# escape-room-riddle-box-11-22_15-05-31.net
KiCad netlist of a schematic drawn in EasyEDA
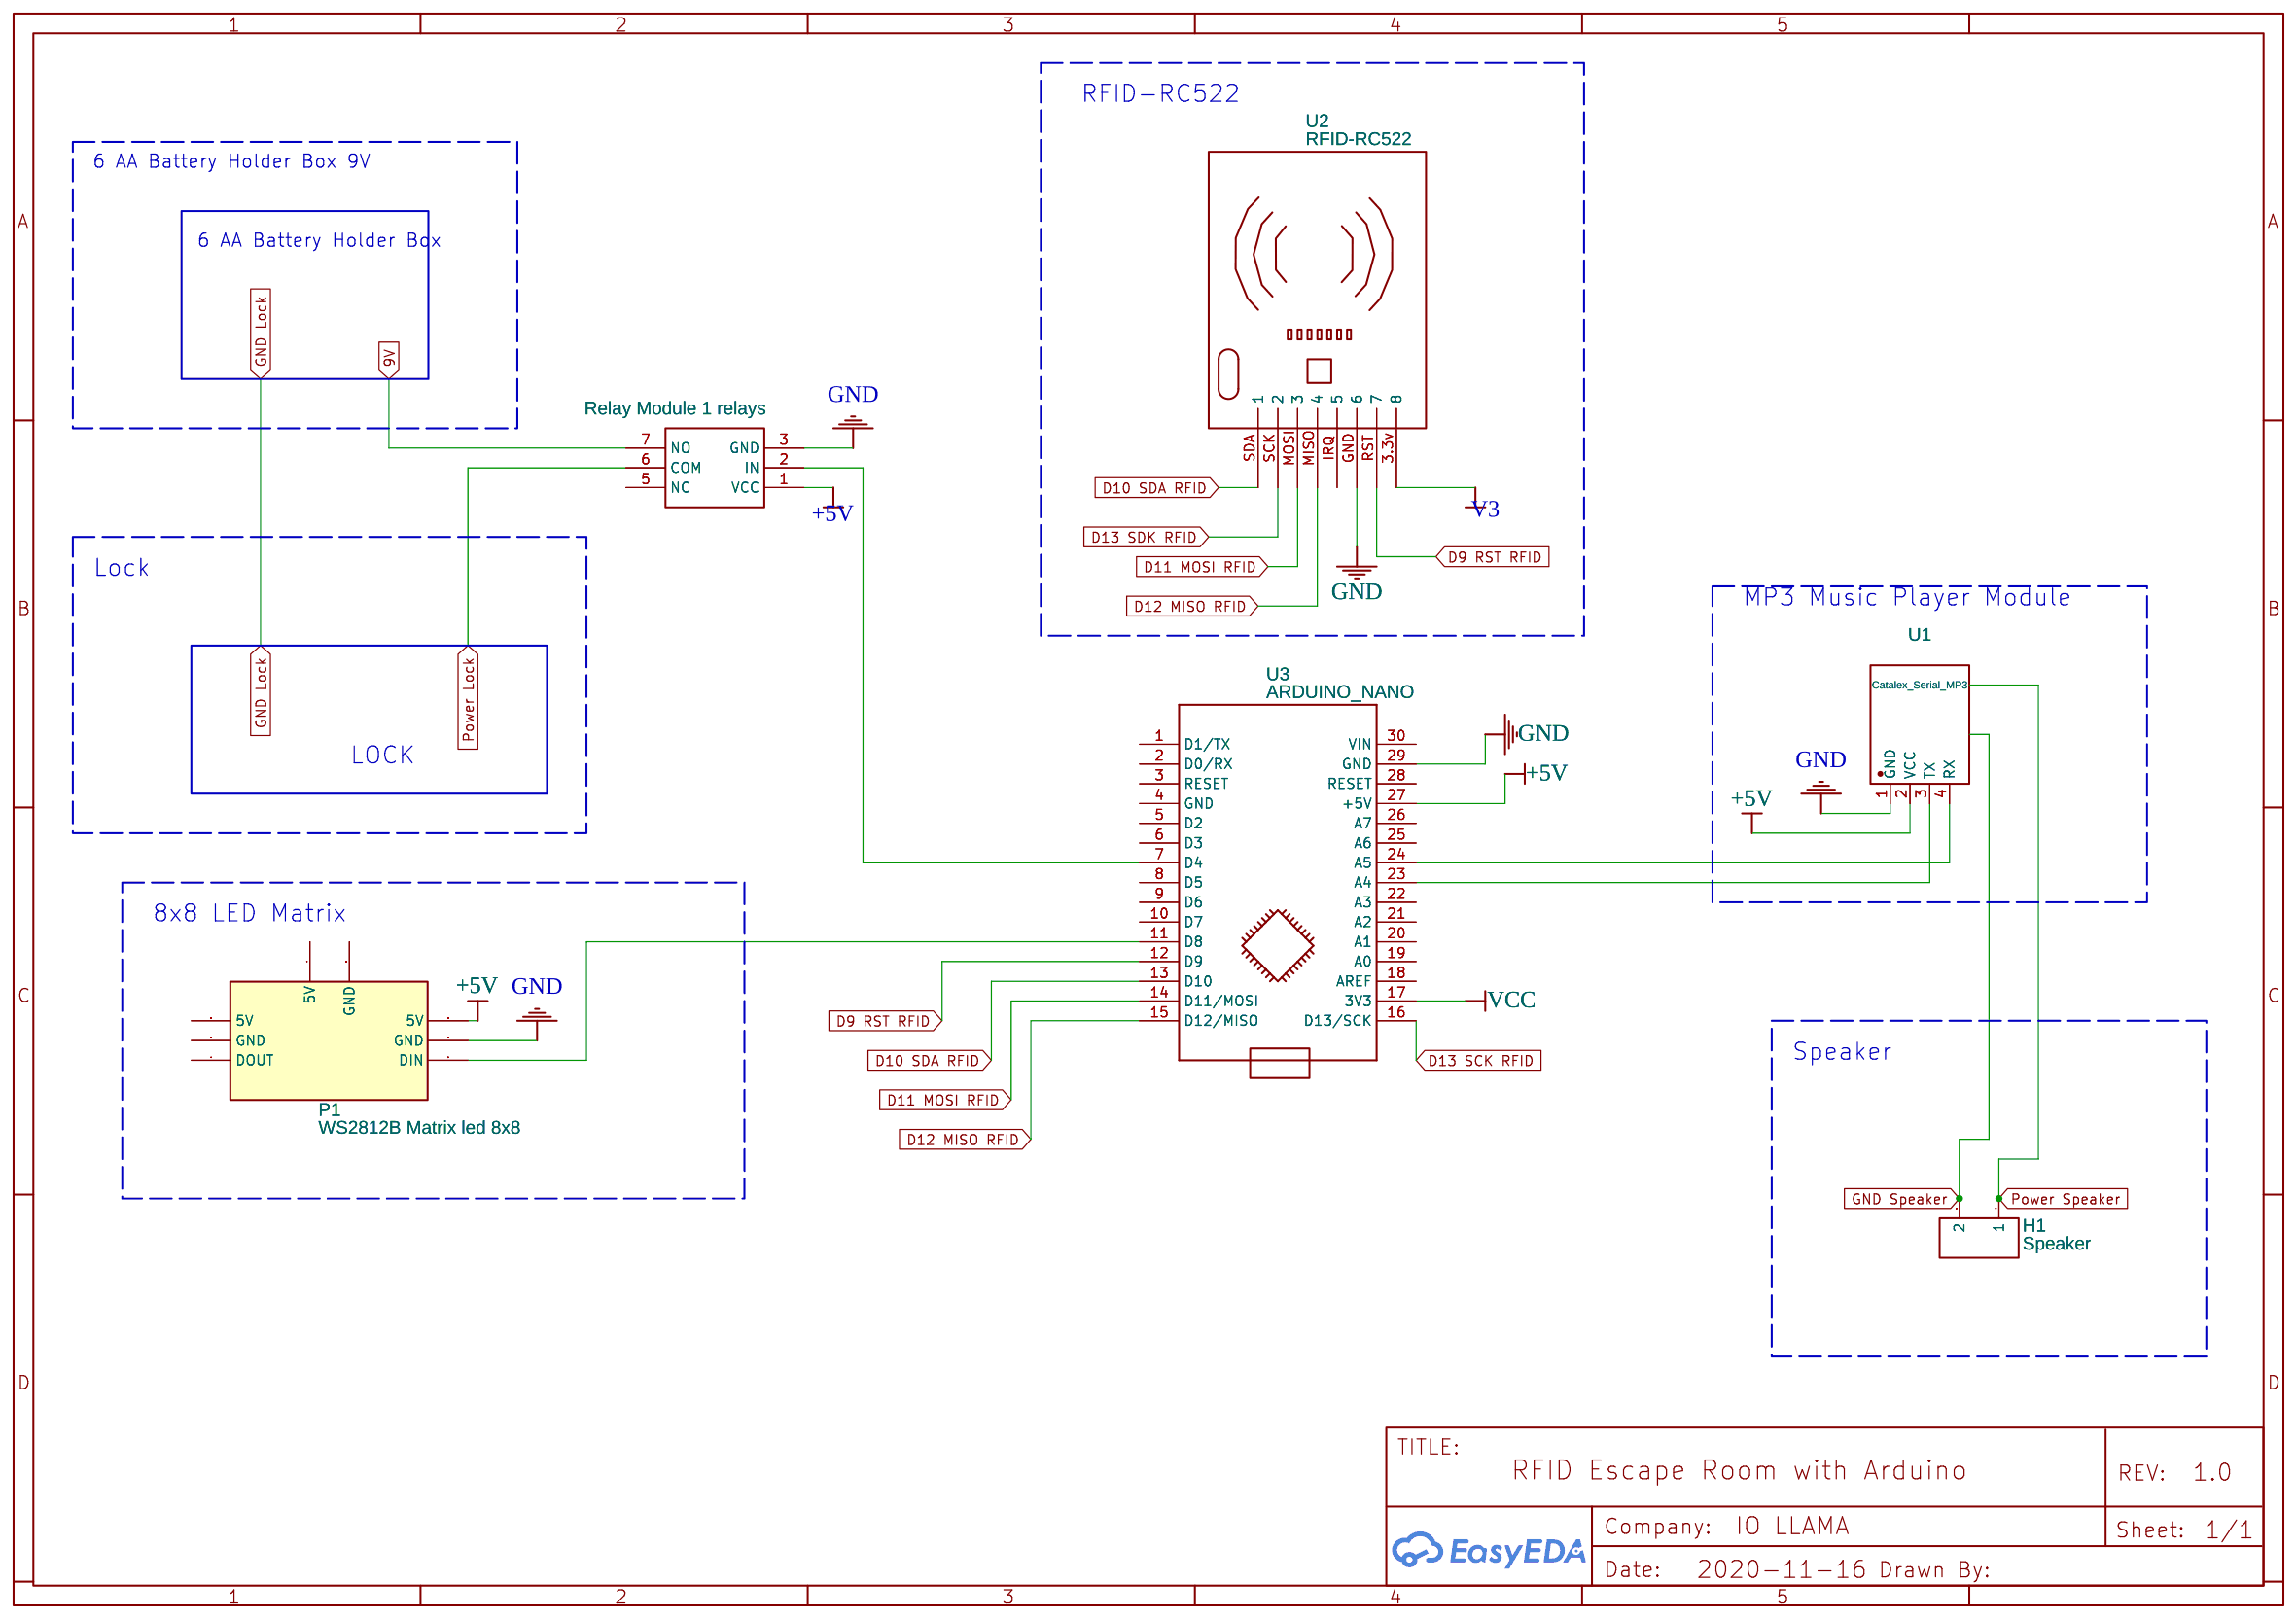
[diagram p0: schematic sheet]

(export (version "E")
  (design (tool "Eeschema 10.0.6"))
  (components
    (comp (ref "H1")
      (value "Speaker")
      (fields (field (name "BOM_Manufacturer Part") "826629-2") (field (name "BOM_Supplier Part") "C86471"))
      (libsource (lib "") (part "Header-Male-2.54_1x2"))
    )
    (comp (ref "P1") (value "WS2812B Matrix led 8x8") (libsource (lib "") (part "WS2812B Matrix led 8x8")))
    (comp (ref "U1")
      (value "Catalex_Serial_MP3")
      (fields (field (name "BOM_Manufacturer Part") "Catalex_Serial_MP3_Board"))
      (libsource (lib "") (part "Catalex_Serial_MP3"))
    )
    (comp (ref "U2")
      (value "RFID-RC522")
      (fields (field (name "BOM_Manufacturer Part") "NXP"))
      (libsource (lib "") (part "RFID-RC522"))
    )
    (comp (ref "U3") (value "ARDUINO_NANO") (libsource (lib "") (part "ARDUINO_NANO")))
    (comp (ref "U4") (value "Relay Module 1 relays") (libsource (lib "") (part "Relay Module 1 relays")))
  )
  (nets
    (net (code "1") (name "+5V") (class "Default")
      (node (ref "P1") (pin "3") (pinfunction "5V_3") (pintype "unspecified"))
      (node (ref "U1") (pin "2") (pinfunction "VCC_2") (pintype "unspecified"))
      (node (ref "U3") (pin "27") (pinfunction "+5V_27") (pintype "unspecified"))
      (node (ref "U4") (pin "1") (pinfunction "VCC_1") (pintype "unspecified"))
    )
    (net (code "2") (name "9V") (class "Default")
      (node (ref "U4") (pin "7") (pinfunction "NO_7") (pintype "unspecified"))
    )
    (net (code "3") (name "D9 RST RFID") (class "Default")
      (node (ref "U2") (pin "RST") (pinfunction "7_RST") (pintype "unspecified"))
      (node (ref "U3") (pin "12") (pinfunction "D9_12") (pintype "unspecified"))
    )
    (net (code "4") (name "D10 SDA RFID") (class "Default")
      (node (ref "U2") (pin "SDA") (pinfunction "1_SDA") (pintype "unspecified"))
      (node (ref "U3") (pin "13") (pinfunction "D10_13") (pintype "unspecified"))
    )
    (net (code "5") (name "D11 MOSI RFID") (class "Default")
      (node (ref "U2") (pin "MOSI") (pinfunction "3_MOSI") (pintype "unspecified"))
      (node (ref "U3") (pin "14") (pinfunction "D11/MOSI_14") (pintype "unspecified"))
    )
    (net (code "6") (name "D12 MISO RFID") (class "Default")
      (node (ref "U2") (pin "MISO") (pinfunction "4_MISO") (pintype "unspecified"))
      (node (ref "U3") (pin "15") (pinfunction "D12/MISO_15") (pintype "unspecified"))
    )
    (net (code "7") (name "D13 SCK RFID") (class "Default")
      (node (ref "U3") (pin "16") (pinfunction "D13/SCK_16") (pintype "unspecified"))
    )
    (net (code "8") (name "D13 SDK RFID") (class "Default")
      (node (ref "U2") (pin "SCK") (pinfunction "2_SCK") (pintype "unspecified"))
    )
    (net (code "9") (name "GND") (class "Default")
      (node (ref "P1") (pin "2") (pinfunction "GND_2") (pintype "unspecified"))
      (node (ref "U1") (pin "1") (pinfunction "GND_1") (pintype "unspecified"))
      (node (ref "U2") (pin "GND") (pinfunction "6_GND") (pintype "unspecified"))
      (node (ref "U3") (pin "29") (pinfunction "GND_29") (pintype "unspecified"))
      (node (ref "U4") (pin "3") (pinfunction "GND_3") (pintype "unspecified"))
    )
    (net (code "11") (name "GND Speaker") (class "Default")
      (node (ref "H1") (pin "2") (pinfunction "2_2") (pintype "unspecified"))
    )
    (net (code "12") (name "Net-(P1-DIN)") (class "Default")
      (node (ref "P1") (pin "1") (pinfunction "DIN_1") (pintype "unspecified"))
      (node (ref "U3") (pin "11") (pinfunction "D8_11") (pintype "unspecified"))
    )
    (net (code "13") (name "Net-(U1-RX)") (class "Default")
      (node (ref "U1") (pin "4") (pinfunction "RX_4") (pintype "unspecified"))
      (node (ref "U3") (pin "24") (pinfunction "A5_24") (pintype "unspecified"))
    )
    (net (code "14") (name "Net-(U1-TX)") (class "Default")
      (node (ref "U1") (pin "3") (pinfunction "TX_3") (pintype "unspecified"))
      (node (ref "U3") (pin "23") (pinfunction "A4_23") (pintype "unspecified"))
    )
    (net (code "15") (name "Net-(U3-D4)") (class "Default")
      (node (ref "U3") (pin "7") (pinfunction "D4_7") (pintype "unspecified"))
      (node (ref "U4") (pin "2") (pinfunction "IN_2") (pintype "unspecified"))
    )
    (net (code "16") (name "Power Lock") (class "Default")
      (node (ref "U4") (pin "6") (pinfunction "COM_6") (pintype "unspecified"))
    )
    (net (code "17") (name "Power Speaker") (class "Default")
      (node (ref "H1") (pin "1") (pinfunction "1_1") (pintype "unspecified"))
    )
    (net (code "18") (name "V3") (class "Default")
      (node (ref "U2") (pin "3.3v") (pinfunction "8_3.3v") (pintype "unspecified"))
    )
    (net (code "19") (name "VCC") (class "Default")
      (node (ref "U3") (pin "17") (pinfunction "3V3_17") (pintype "unspecified"))
    )
    (net (code "20") (name "unconnected-(P1-5V-Pad6)") (class "Default")
      (node (ref "P1") (pin "6") (pinfunction "5V_6") (pintype "unspecified"))
    )
    (net (code "21") (name "unconnected-(P1-5V-Pad7)") (class "Default")
      (node (ref "P1") (pin "7") (pinfunction "5V_7") (pintype "unspecified"))
    )
    (net (code "22") (name "unconnected-(P1-DOUT-Pad4)") (class "Default")
      (node (ref "P1") (pin "4") (pinfunction "DOUT_4") (pintype "unspecified"))
    )
    (net (code "23") (name "unconnected-(P1-GND-Pad5)") (class "Default")
      (node (ref "P1") (pin "5") (pinfunction "GND_5") (pintype "unspecified"))
    )
    (net (code "24") (name "unconnected-(P1-GND-Pad8)") (class "Default")
      (node (ref "P1") (pin "8") (pinfunction "GND_8") (pintype "unspecified"))
    )
    (net (code "25") (name "unconnected-(U2-5-PadIRQ)") (class "Default")
      (node (ref "U2") (pin "IRQ") (pinfunction "5_IRQ") (pintype "unspecified"))
    )
    (net (code "26") (name "unconnected-(U3-A0-Pad19)") (class "Default")
      (node (ref "U3") (pin "19") (pinfunction "A0_19") (pintype "unspecified"))
    )
    (net (code "27") (name "unconnected-(U3-A1-Pad20)") (class "Default")
      (node (ref "U3") (pin "20") (pinfunction "A1_20") (pintype "unspecified"))
    )
    (net (code "28") (name "unconnected-(U3-A2-Pad21)") (class "Default")
      (node (ref "U3") (pin "21") (pinfunction "A2_21") (pintype "unspecified"))
    )
    (net (code "29") (name "unconnected-(U3-A3-Pad22)") (class "Default")
      (node (ref "U3") (pin "22") (pinfunction "A3_22") (pintype "unspecified"))
    )
    (net (code "30") (name "unconnected-(U3-A6-Pad25)") (class "Default")
      (node (ref "U3") (pin "25") (pinfunction "A6_25") (pintype "unspecified"))
    )
    (net (code "31") (name "unconnected-(U3-A7-Pad26)") (class "Default")
      (node (ref "U3") (pin "26") (pinfunction "A7_26") (pintype "unspecified"))
    )
    (net (code "32") (name "unconnected-(U3-AREF-Pad18)") (class "Default")
      (node (ref "U3") (pin "18") (pinfunction "AREF_18") (pintype "unspecified"))
    )
    (net (code "33") (name "unconnected-(U3-D0{slash}RX-Pad2)") (class "Default")
      (node (ref "U3") (pin "2") (pinfunction "D0/RX_2") (pintype "unspecified"))
    )
    (net (code "34") (name "unconnected-(U3-D1{slash}TX-Pad1)") (class "Default")
      (node (ref "U3") (pin "1") (pinfunction "D1/TX_1") (pintype "unspecified"))
    )
    (net (code "35") (name "unconnected-(U3-D2-Pad5)") (class "Default")
      (node (ref "U3") (pin "5") (pinfunction "D2_5") (pintype "unspecified"))
    )
    (net (code "36") (name "unconnected-(U3-D3-Pad6)") (class "Default")
      (node (ref "U3") (pin "6") (pinfunction "D3_6") (pintype "unspecified"))
    )
    (net (code "37") (name "unconnected-(U3-D5-Pad8)") (class "Default")
      (node (ref "U3") (pin "8") (pinfunction "D5_8") (pintype "unspecified"))
    )
    (net (code "38") (name "unconnected-(U3-D6-Pad9)") (class "Default")
      (node (ref "U3") (pin "9") (pinfunction "D6_9") (pintype "unspecified"))
    )
    (net (code "39") (name "unconnected-(U3-D7-Pad10)") (class "Default")
      (node (ref "U3") (pin "10") (pinfunction "D7_10") (pintype "unspecified"))
    )
    (net (code "40") (name "unconnected-(U3-GND-Pad4)") (class "Default")
      (node (ref "U3") (pin "4") (pinfunction "GND_4") (pintype "unspecified"))
    )
    (net (code "41") (name "unconnected-(U3-RESET-Pad3)") (class "Default")
      (node (ref "U3") (pin "3") (pinfunction "RESET_3") (pintype "unspecified"))
    )
    (net (code "42") (name "unconnected-(U3-RESET-Pad28)") (class "Default")
      (node (ref "U3") (pin "28") (pinfunction "RESET_28") (pintype "unspecified"))
    )
    (net (code "43") (name "unconnected-(U3-VIN-Pad30)") (class "Default")
      (node (ref "U3") (pin "30") (pinfunction "VIN_30") (pintype "unspecified"))
    )
    (net (code "44") (name "unconnected-(U4-NC-Pad5)") (class "Default")
      (node (ref "U4") (pin "5") (pinfunction "NC_5") (pintype "unspecified"))
    )
  )
)
